# S7G2_footprint_with_caps.net
KiCad netlist of a schematic drawn in EAGLE
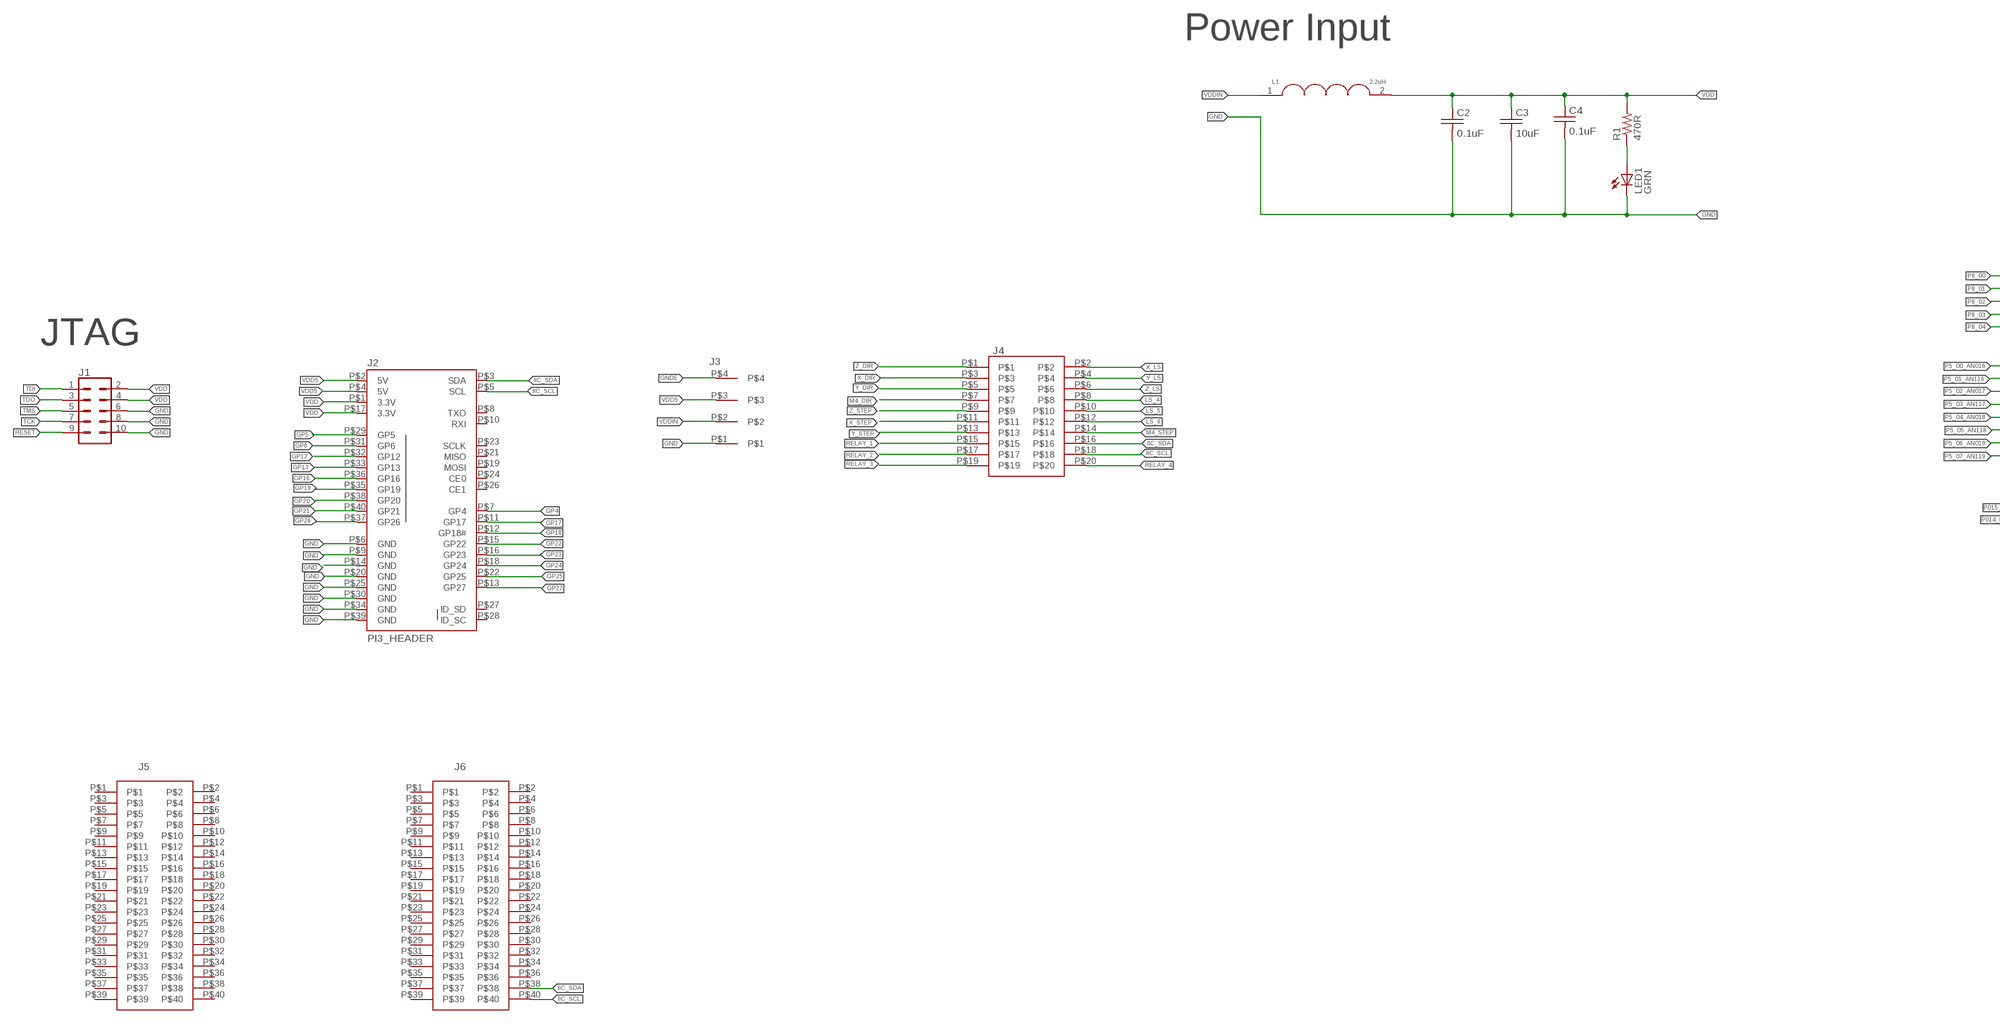
[diagram p0: schematic, sheet 1, part 1 of 3]
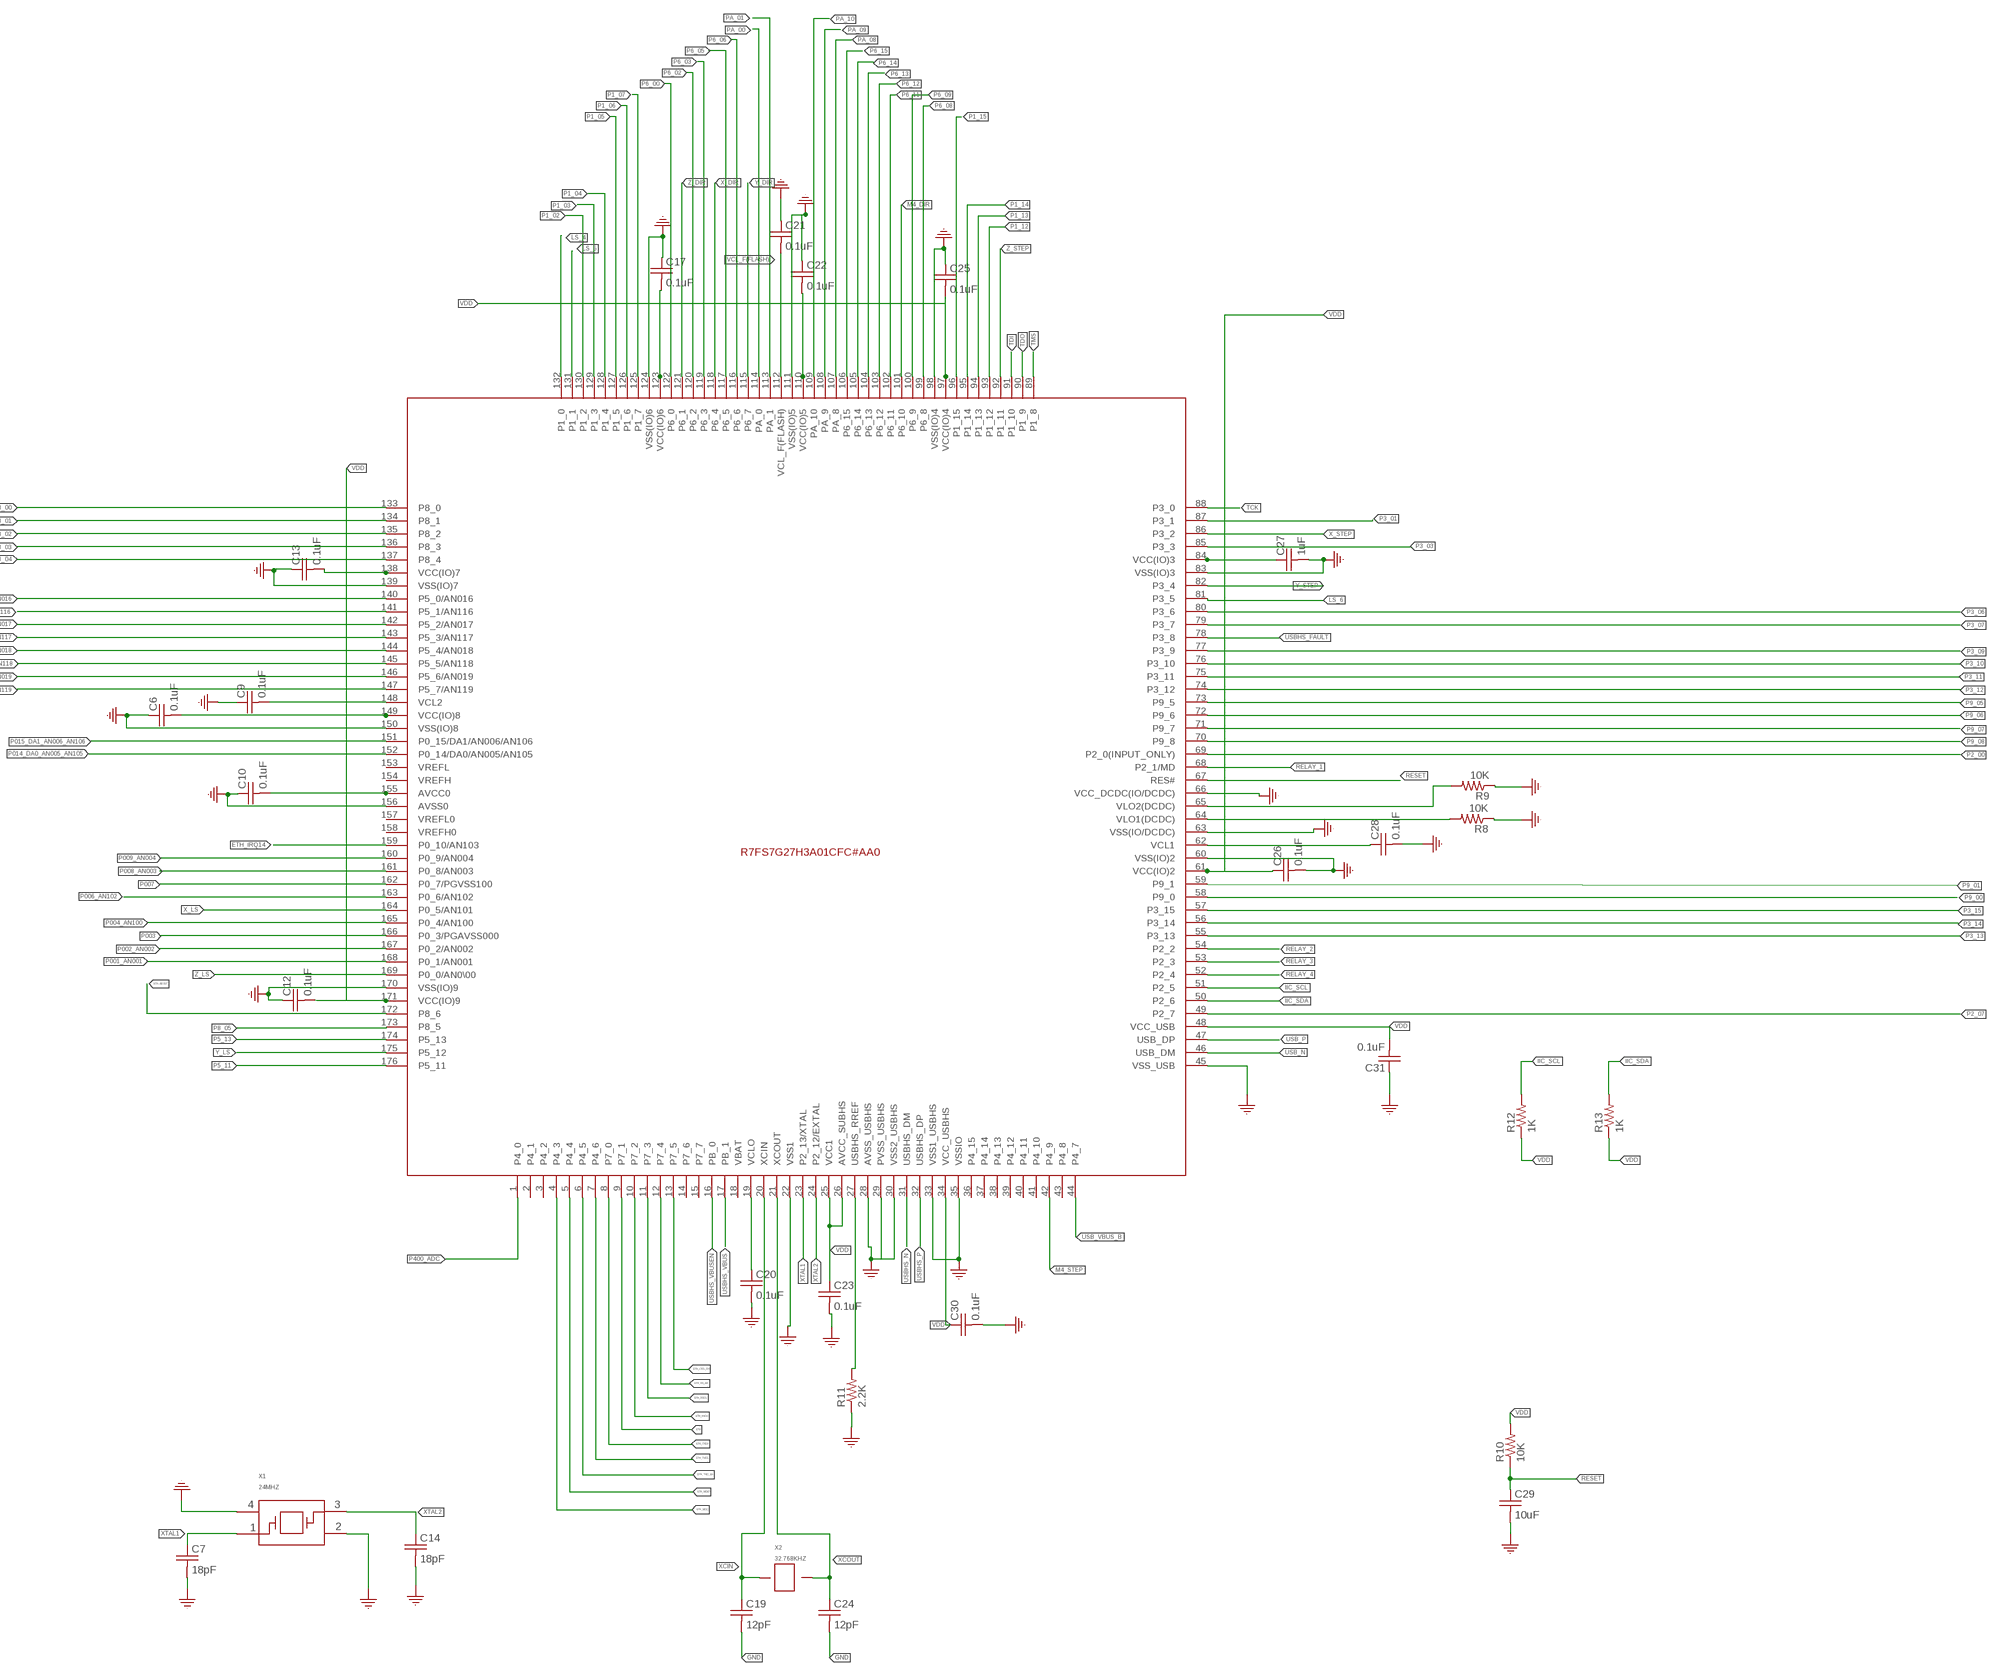
[diagram p1: schematic, sheet 1, part 2 of 3]
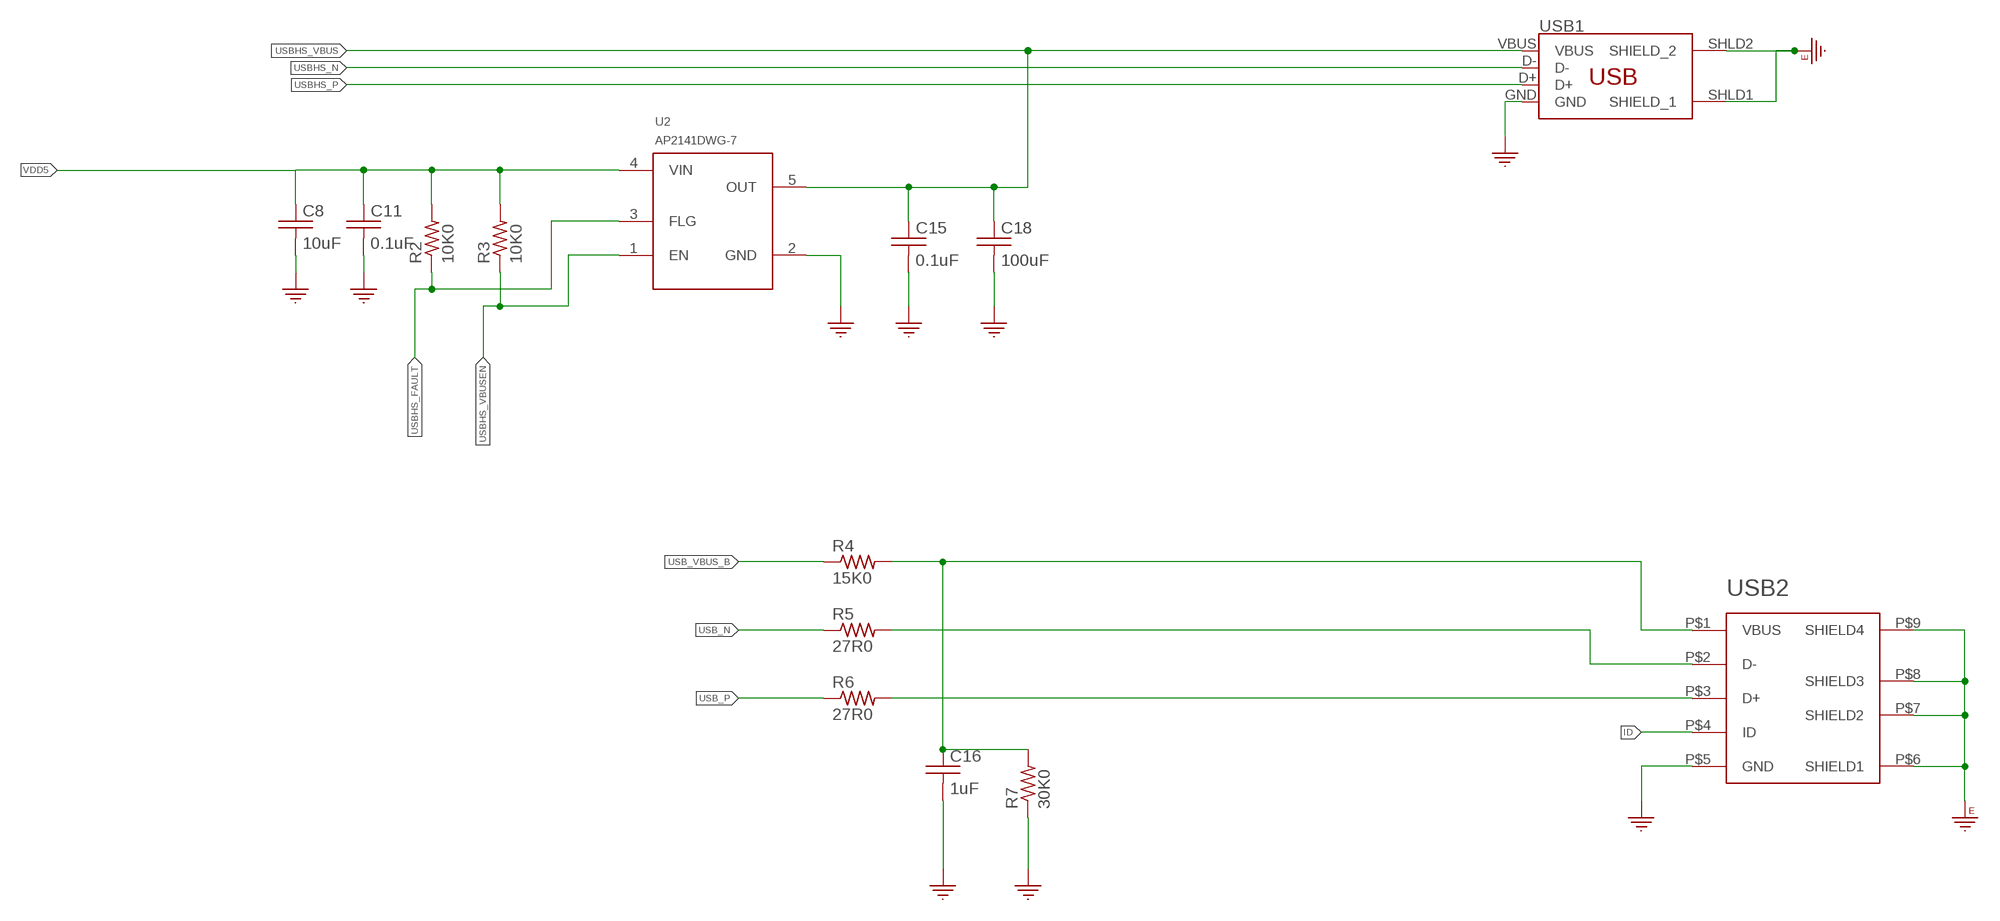
[diagram p2: schematic, sheet 1, part 3 of 3]

(export (version "E")
  (design (tool "Eeschema 10.0.6"))
  (components
    (comp (ref "C2")
      (value "0.1uF")
      (footprint "eagle-import:0402")
      (libsource (lib "eagle-import") (part "C_0402"))
    )
    (comp (ref "C3")
      (value "10uF")
      (footprint "eagle-import:0402")
      (libsource (lib "eagle-import") (part "C_0402"))
    )
    (comp (ref "C4")
      (value "0.1uF")
      (footprint "eagle-import:0402")
      (libsource (lib "eagle-import") (part "C_0402"))
    )
    (comp (ref "C6")
      (value "0.1uF")
      (footprint "eagle-import:0402")
      (libsource (lib "eagle-import") (part "C_0402"))
    )
    (comp (ref "C7")
      (value "18pF")
      (footprint "eagle-import:0402")
      (libsource (lib "eagle-import") (part "C_0402"))
    )
    (comp (ref "C8")
      (value "10uF")
      (footprint "eagle-import:0402")
      (libsource (lib "eagle-import") (part "C_0402"))
    )
    (comp (ref "C9")
      (value "0.1uF")
      (footprint "eagle-import:0402")
      (libsource (lib "eagle-import") (part "C_0402"))
    )
    (comp (ref "C10")
      (value "0.1uF")
      (footprint "eagle-import:0402")
      (libsource (lib "eagle-import") (part "C_0402"))
    )
    (comp (ref "C11")
      (value "0.1uF")
      (footprint "eagle-import:0402")
      (libsource (lib "eagle-import") (part "C_0402"))
    )
    (comp (ref "C12")
      (value "0.1uF")
      (footprint "eagle-import:0402")
      (libsource (lib "eagle-import") (part "C_0402"))
    )
    (comp (ref "C13")
      (value "0.1uF")
      (footprint "eagle-import:0402")
      (libsource (lib "eagle-import") (part "C_0402"))
    )
    (comp (ref "C14")
      (value "18pF")
      (footprint "eagle-import:0402")
      (libsource (lib "eagle-import") (part "C_0402"))
    )
    (comp (ref "C15")
      (value "0.1uF")
      (footprint "eagle-import:0402")
      (libsource (lib "eagle-import") (part "C_0402"))
    )
    (comp (ref "C16")
      (value "1uF")
      (footprint "eagle-import:0402")
      (libsource (lib "eagle-import") (part "C_0402"))
    )
    (comp (ref "C17")
      (value "0.1uF")
      (footprint "eagle-import:0402")
      (libsource (lib "eagle-import") (part "C_0402"))
    )
    (comp (ref "C18")
      (value "100uF")
      (footprint "eagle-import:C1210")
      (libsource (lib "eagle-import") (part "C_1210"))
    )
    (comp (ref "C19")
      (value "12pF")
      (footprint "eagle-import:0402")
      (libsource (lib "eagle-import") (part "C_0402"))
    )
    (comp (ref "C20")
      (value "0.1uF")
      (footprint "eagle-import:0402")
      (libsource (lib "eagle-import") (part "C_0402"))
    )
    (comp (ref "C21")
      (value "0.1uF")
      (footprint "eagle-import:0402")
      (libsource (lib "eagle-import") (part "C_0402"))
    )
    (comp (ref "C22")
      (value "0.1uF")
      (footprint "eagle-import:0402")
      (libsource (lib "eagle-import") (part "C_0402"))
    )
    (comp (ref "C23")
      (value "0.1uF")
      (footprint "eagle-import:0402")
      (libsource (lib "eagle-import") (part "C_0402"))
    )
    (comp (ref "C24")
      (value "12pF")
      (footprint "eagle-import:0402")
      (libsource (lib "eagle-import") (part "C_0402"))
    )
    (comp (ref "C25")
      (value "0.1uF")
      (footprint "eagle-import:0402")
      (libsource (lib "eagle-import") (part "C_0402"))
    )
    (comp (ref "C26")
      (value "0.1uF")
      (footprint "eagle-import:0402")
      (libsource (lib "eagle-import") (part "C_0402"))
    )
    (comp (ref "C27")
      (value "1uF")
      (footprint "eagle-import:0402")
      (libsource (lib "eagle-import") (part "C_0402"))
    )
    (comp (ref "C28")
      (value "0.1uF")
      (footprint "eagle-import:0402")
      (libsource (lib "eagle-import") (part "C_0402"))
    )
    (comp (ref "C29")
      (value "10uF")
      (footprint "eagle-import:0402")
      (libsource (lib "eagle-import") (part "C_0402"))
    )
    (comp (ref "C30")
      (value "0.1uF")
      (footprint "eagle-import:0402")
      (libsource (lib "eagle-import") (part "C_0402"))
    )
    (comp (ref "C31")
      (value "0.1uF")
      (footprint "eagle-import:0402")
      (libsource (lib "eagle-import") (part "C_0402"))
    )
    (comp (ref "J1")
      (value "CONN_05X2PTH")
      (footprint "eagle-import:2X5")
      (libsource (lib "eagle-import") (part "CONN_05X2PTH"))
    )
    (comp (ref "J2")
      (value "PI3_HEADER")
      (footprint "eagle-import:HEADER_2_X_20_.1_INCH")
      (libsource (lib "eagle-import") (part "PI3_HEADER"))
    )
    (comp (ref "J3")
      (value "3.81MM_1_X_4_RT_ANGLE_PLUG_HEADER")
      (footprint "eagle-import:1X4_3.81MM_PITCH")
      (libsource (lib "eagle-import") (part "3.81MM_1_X_4_RT_ANGLE_PLUG_HEADER"))
    )
    (comp (ref "J4")
      (value "2_X_10_HEADER_GENERIC")
      (footprint "eagle-import:2_X_10_.1_INCH")
      (libsource (lib "eagle-import") (part "2_X_10_HEADER_GENERIC"))
    )
    (comp (ref "J5")
      (value "HEADER_2_X_20_GENERIC")
      (footprint "eagle-import:HEADER_2_X_20_.1_INCH")
      (libsource (lib "eagle-import") (part "HEADER_2_X_20_GENERIC"))
    )
    (comp (ref "J6")
      (value "HEADER_2_X_20_GENERIC")
      (footprint "eagle-import:HEADER_2_X_20_.1_INCH")
      (libsource (lib "eagle-import") (part "HEADER_2_X_20_GENERIC"))
    )
    (comp (ref "L1")
      (value "2.2uH")
      (footprint "eagle-import:1008_(2520_METRIC)")
      (libsource (lib "eagle-import") (part "INDUCTOR_1008_2.2_MH_1.3A"))
    )
    (comp (ref "LED1")
      (value "LED_0805_GREEN")
      (footprint "eagle-import:LED_0805_GREEN")
      (libsource (lib "eagle-import") (part "LED_0805_GREEN"))
    )
    (comp (ref "R1")
      (value "470R")
      (footprint "eagle-import:0402")
      (libsource (lib "eagle-import") (part "R_0402"))
    )
    (comp (ref "R2")
      (value "10K0")
      (footprint "eagle-import:0402")
      (libsource (lib "eagle-import") (part "R_0402"))
    )
    (comp (ref "R3")
      (value "10K0")
      (footprint "eagle-import:0402")
      (libsource (lib "eagle-import") (part "R_0402"))
    )
    (comp (ref "R4")
      (value "15K0")
      (footprint "eagle-import:0402")
      (libsource (lib "eagle-import") (part "R_0402"))
    )
    (comp (ref "R5")
      (value "27R0")
      (footprint "eagle-import:0402")
      (libsource (lib "eagle-import") (part "R_0402"))
    )
    (comp (ref "R6")
      (value "27R0")
      (footprint "eagle-import:0402")
      (libsource (lib "eagle-import") (part "R_0402"))
    )
    (comp (ref "R7")
      (value "30K0")
      (footprint "eagle-import:0402")
      (libsource (lib "eagle-import") (part "R_0402"))
    )
    (comp (ref "R8")
      (value "10K")
      (footprint "eagle-import:0402")
      (libsource (lib "eagle-import") (part "R_0402"))
    )
    (comp (ref "R9")
      (value "10K")
      (footprint "eagle-import:0402")
      (libsource (lib "eagle-import") (part "R_0402"))
    )
    (comp (ref "R10")
      (value "10K")
      (footprint "eagle-import:0402")
      (libsource (lib "eagle-import") (part "R_0402"))
    )
    (comp (ref "R11")
      (value "2.2K")
      (footprint "eagle-import:0402")
      (libsource (lib "eagle-import") (part "R_0402"))
    )
    (comp (ref "R12")
      (value "1K")
      (footprint "eagle-import:0402")
      (libsource (lib "eagle-import") (part "R_0402"))
    )
    (comp (ref "R13")
      (value "1K")
      (footprint "eagle-import:0402")
      (libsource (lib "eagle-import") (part "R_0402"))
    )
    (comp (ref "U2")
      (value "AP2141DWG-5")
      (footprint "eagle-import:SOT-23-5")
      (libsource (lib "eagle-import") (part "AP2141DWG-5"))
    )
    (comp (ref "U5")
      (value "S7G2_X_176")
      (footprint "eagle-import:LQFP176_24X24")
      (libsource (lib "eagle-import") (part "S7G2_X_176"))
    )
    (comp (ref "USB1")
      (value "USB_A")
      (footprint "eagle-import:USB_A_SMT")
      (libsource (lib "eagle-import") (part "USB_A"))
    )
    (comp (ref "USB2")
      (value "USB_MICRO-B")
      (footprint "eagle-import:USB_MICRO-B")
      (libsource (lib "eagle-import") (part "USB_MICRO-B"))
    )
    (comp (ref "X1")
      (value "24MHZ")
      (footprint "eagle-import:SMD_3225")
      (libsource (lib "eagle-import") (part "XTAL_24_MHZ"))
    )
    (comp (ref "X2")
      (value "32.768KHZ")
      (footprint "eagle-import:SMD_X_2_PADS")
      (libsource (lib "eagle-import") (part "XTAL_32.768KHZ"))
    )
  )
  (nets
    (net (code "1") (name "ETH") (class "Default")
      (node (ref "U5") (pin "9") (pinfunction "P7_1_9") (pintype "bidirectional"))
    )
    (net (code "2") (name "ETH_CRS_DV") (class "Default")
      (node (ref "U5") (pin "13") (pinfunction "P7_5_13") (pintype "bidirectional"))
    )
    (net (code "3") (name "ETH_IRQ14") (class "Default")
      (node (ref "U5") (pin "159") (pinfunction "P0_10/AN103_159") (pintype "bidirectional"))
    )
    (net (code "4") (name "ETH_MDC") (class "Default")
      (node (ref "U5") (pin "4") (pinfunction "P4_3_4") (pintype "bidirectional"))
    )
    (net (code "5") (name "ETH_MDIO") (class "Default")
      (node (ref "U5") (pin "5") (pinfunction "P4_4_5") (pintype "bidirectional"))
    )
    (net (code "6") (name "ETH_RESET") (class "Default")
      (node (ref "U5") (pin "172") (pinfunction "P8_6_172") (pintype "bidirectional"))
    )
    (net (code "7") (name "ETH_RXD0") (class "Default")
      (node (ref "U5") (pin "10") (pinfunction "P7_2_10") (pintype "bidirectional"))
    )
    (net (code "8") (name "ETH_RXD1") (class "Default")
      (node (ref "U5") (pin "11") (pinfunction "P7_3_11") (pintype "bidirectional"))
    )
    (net (code "9") (name "ETH_RX_ER") (class "Default")
      (node (ref "U5") (pin "12") (pinfunction "P7_4_12") (pintype "bidirectional"))
    )
    (net (code "10") (name "ETH_TXD0") (class "Default")
      (node (ref "U5") (pin "8") (pinfunction "P7_0_8") (pintype "bidirectional"))
    )
    (net (code "11") (name "ETH_TXD1") (class "Default")
      (node (ref "U5") (pin "7") (pinfunction "P4_6_7") (pintype "bidirectional"))
    )
    (net (code "12") (name "ETH_TXD_EN") (class "Default")
      (node (ref "U5") (pin "6") (pinfunction "P4_5_6") (pintype "bidirectional"))
    )
    (net (code "13") (name "GND") (class "Default")
      (node (ref "C10") (pin "P$1") (pinfunction "1_P$1") (pintype "passive"))
      (node (ref "C11") (pin "P$2") (pinfunction "2_P$2") (pintype "passive"))
      (node (ref "C12") (pin "P$1") (pinfunction "1_P$1") (pintype "passive"))
      (node (ref "C13") (pin "P$1") (pinfunction "1_P$1") (pintype "passive"))
      (node (ref "C14") (pin "P$2") (pinfunction "2_P$2") (pintype "passive"))
      (node (ref "C15") (pin "P$2") (pinfunction "2_P$2") (pintype "passive"))
      (node (ref "C16") (pin "P$2") (pinfunction "2_P$2") (pintype "passive"))
      (node (ref "C17") (pin "P$1") (pinfunction "1_P$1") (pintype "passive"))
      (node (ref "C18") (pin "2") (pinfunction "2_2") (pintype "passive"))
      (node (ref "C19") (pin "P$2") (pinfunction "2_P$2") (pintype "passive"))
      (node (ref "C2") (pin "P$2") (pinfunction "2_P$2") (pintype "passive"))
      (node (ref "C20") (pin "P$2") (pinfunction "2_P$2") (pintype "passive"))
      (node (ref "C21") (pin "P$1") (pinfunction "1_P$1") (pintype "passive"))
      (node (ref "C22") (pin "P$1") (pinfunction "1_P$1") (pintype "passive"))
      (node (ref "C23") (pin "P$2") (pinfunction "2_P$2") (pintype "passive"))
      (node (ref "C24") (pin "P$2") (pinfunction "2_P$2") (pintype "passive"))
      (node (ref "C25") (pin "P$1") (pinfunction "1_P$1") (pintype "passive"))
      (node (ref "C26") (pin "P$2") (pinfunction "2_P$2") (pintype "passive"))
      (node (ref "C27") (pin "P$2") (pinfunction "2_P$2") (pintype "passive"))
      (node (ref "C28") (pin "P$2") (pinfunction "2_P$2") (pintype "passive"))
      (node (ref "C29") (pin "P$2") (pinfunction "2_P$2") (pintype "passive"))
      (node (ref "C3") (pin "P$2") (pinfunction "2_P$2") (pintype "passive"))
      (node (ref "C30") (pin "P$2") (pinfunction "2_P$2") (pintype "passive"))
      (node (ref "C31") (pin "P$1") (pinfunction "1_P$1") (pintype "passive"))
      (node (ref "C4") (pin "P$2") (pinfunction "2_P$2") (pintype "passive"))
      (node (ref "C6") (pin "P$1") (pinfunction "1_P$1") (pintype "passive"))
      (node (ref "C7") (pin "P$2") (pinfunction "2_P$2") (pintype "passive"))
      (node (ref "C8") (pin "P$2") (pinfunction "2_P$2") (pintype "passive"))
      (node (ref "C9") (pin "P$1") (pinfunction "1_P$1") (pintype "passive"))
      (node (ref "J1") (pin "10") (pinfunction "10_10") (pintype "passive"))
      (node (ref "J1") (pin "6") (pinfunction "6_6") (pintype "passive"))
      (node (ref "J1") (pin "8") (pinfunction "8_8") (pintype "passive"))
      (node (ref "J2") (pin "P$14") (pinfunction "GND_P$14") (pintype "power_in"))
      (node (ref "J2") (pin "P$20") (pinfunction "GND_P$20") (pintype "power_in"))
      (node (ref "J2") (pin "P$25") (pinfunction "GND_P$25") (pintype "power_in"))
      (node (ref "J2") (pin "P$30") (pinfunction "GND_P$30") (pintype "power_in"))
      (node (ref "J2") (pin "P$34") (pinfunction "GND_P$34") (pintype "power_in"))
      (node (ref "J2") (pin "P$39") (pinfunction "GND_P$39") (pintype "power_in"))
      (node (ref "J2") (pin "P$6") (pinfunction "GND_P$6") (pintype "power_in"))
      (node (ref "J2") (pin "P$9") (pinfunction "GND_P$9") (pintype "power_in"))
      (node (ref "J3") (pin "P$1") (pinfunction "P$1_P$1") (pintype "bidirectional"))
      (node (ref "LED1") (pin "C") (pinfunction "C_C") (pintype "passive"))
      (node (ref "R11") (pin "P$1") (pinfunction "1_P$1") (pintype "passive"))
      (node (ref "R7") (pin "P$1") (pinfunction "1_P$1") (pintype "passive"))
      (node (ref "R8") (pin "P$1") (pinfunction "1_P$1") (pintype "passive"))
      (node (ref "R9") (pin "P$1") (pinfunction "1_P$1") (pintype "passive"))
      (node (ref "U2") (pin "2") (pinfunction "GND_2") (pintype "input"))
      (node (ref "U5") (pin "111") (pinfunction "VSS(IO)5_111") (pintype "bidirectional"))
      (node (ref "U5") (pin "124") (pinfunction "VSS(IO)6_124") (pintype "bidirectional"))
      (node (ref "U5") (pin "139") (pinfunction "VSS(IO)7_139") (pintype "bidirectional"))
      (node (ref "U5") (pin "150") (pinfunction "VSS(IO)8_150") (pintype "bidirectional"))
      (node (ref "U5") (pin "156") (pinfunction "AVSS0_156") (pintype "bidirectional"))
      (node (ref "U5") (pin "170") (pinfunction "VSS(IO)9_170") (pintype "bidirectional"))
      (node (ref "U5") (pin "22") (pinfunction "VSS1_22") (pintype "bidirectional"))
      (node (ref "U5") (pin "28") (pinfunction "AVSS_USBHS_28") (pintype "bidirectional"))
      (node (ref "U5") (pin "29") (pinfunction "PVSS_USBHS_29") (pintype "bidirectional"))
      (node (ref "U5") (pin "30") (pinfunction "VSS2_USBHS_30") (pintype "bidirectional"))
      (node (ref "U5") (pin "33") (pinfunction "VSS1_USBHS_33") (pintype "bidirectional"))
      (node (ref "U5") (pin "35") (pinfunction "VSSIO_35") (pintype "bidirectional"))
      (node (ref "U5") (pin "45") (pinfunction "VSS_USB_45") (pintype "bidirectional"))
      (node (ref "U5") (pin "60") (pinfunction "VSS(IO)2_60") (pintype "bidirectional"))
      (node (ref "U5") (pin "63") (pinfunction "VSS(IO/DCDC)_63") (pintype "bidirectional"))
      (node (ref "U5") (pin "66") (pinfunction "VCC_DCDC(IO/DCDC)_66") (pintype "bidirectional"))
      (node (ref "U5") (pin "83") (pinfunction "VSS(IO)3_83") (pintype "bidirectional"))
      (node (ref "U5") (pin "98") (pinfunction "VSS(IO)4_98") (pintype "bidirectional"))
      (node (ref "USB1") (pin "GND") (pinfunction "GND_GND") (pintype "power_in"))
      (node (ref "USB2") (pin "P$5") (pinfunction "GND_P$5") (pintype "bidirectional"))
      (node (ref "X1") (pin "2") (pinfunction "2_2") (pintype "bidirectional"))
      (node (ref "X1") (pin "4") (pinfunction "4_4") (pintype "bidirectional"))
    )
    (net (code "14") (name "GNDE") (class "Default")
      (node (ref "J3") (pin "P$4") (pinfunction "P$4_P$4") (pintype "bidirectional"))
      (node (ref "USB1") (pin "SHLD1") (pinfunction "SHIELD_1_SHLD1") (pintype "bidirectional"))
      (node (ref "USB1") (pin "SHLD2") (pinfunction "SHIELD_2_SHLD2") (pintype "bidirectional"))
      (node (ref "USB2") (pin "P$6") (pinfunction "SHIELD1_P$6") (pintype "bidirectional"))
      (node (ref "USB2") (pin "P$7") (pinfunction "SHIELD2_P$7") (pintype "bidirectional"))
      (node (ref "USB2") (pin "P$8") (pinfunction "SHIELD3_P$8") (pintype "bidirectional"))
      (node (ref "USB2") (pin "P$9") (pinfunction "SHIELD4_P$9") (pintype "bidirectional"))
    )
    (net (code "15") (name "GP4") (class "Default")
      (node (ref "J2") (pin "P$7") (pinfunction "GP4_P$7") (pintype "bidirectional"))
    )
    (net (code "16") (name "GP5") (class "Default")
      (node (ref "J2") (pin "P$29") (pinfunction "GP5_P$29") (pintype "bidirectional"))
    )
    (net (code "17") (name "GP6") (class "Default")
      (node (ref "J2") (pin "P$31") (pinfunction "GP6_P$31") (pintype "bidirectional"))
    )
    (net (code "18") (name "GP12") (class "Default")
      (node (ref "J2") (pin "P$32") (pinfunction "GP12_P$32") (pintype "bidirectional"))
    )
    (net (code "19") (name "GP13") (class "Default")
      (node (ref "J2") (pin "P$33") (pinfunction "GP13_P$33") (pintype "bidirectional"))
    )
    (net (code "20") (name "GP16") (class "Default")
      (node (ref "J2") (pin "P$36") (pinfunction "GP16_P$36") (pintype "bidirectional"))
    )
    (net (code "21") (name "GP17") (class "Default")
      (node (ref "J2") (pin "P$11") (pinfunction "GP17_P$11") (pintype "bidirectional"))
    )
    (net (code "22") (name "GP18") (class "Default")
      (node (ref "J2") (pin "P$12") (pinfunction "GP18#_P$12") (pintype "bidirectional"))
    )
    (net (code "23") (name "GP19") (class "Default")
      (node (ref "J2") (pin "P$35") (pinfunction "GP19_P$35") (pintype "bidirectional"))
    )
    (net (code "24") (name "GP20") (class "Default")
      (node (ref "J2") (pin "P$38") (pinfunction "GP20_P$38") (pintype "bidirectional"))
    )
    (net (code "25") (name "GP21") (class "Default")
      (node (ref "J2") (pin "P$40") (pinfunction "GP21_P$40") (pintype "bidirectional"))
    )
    (net (code "26") (name "GP22") (class "Default")
      (node (ref "J2") (pin "P$15") (pinfunction "GP22_P$15") (pintype "bidirectional"))
    )
    (net (code "27") (name "GP23") (class "Default")
      (node (ref "J2") (pin "P$16") (pinfunction "GP23_P$16") (pintype "bidirectional"))
    )
    (net (code "28") (name "GP24") (class "Default")
      (node (ref "J2") (pin "P$18") (pinfunction "GP24_P$18") (pintype "bidirectional"))
    )
    (net (code "29") (name "GP25") (class "Default")
      (node (ref "J2") (pin "P$22") (pinfunction "GP25_P$22") (pintype "bidirectional"))
    )
    (net (code "30") (name "GP26") (class "Default")
      (node (ref "J2") (pin "P$37") (pinfunction "GP26_P$37") (pintype "bidirectional"))
    )
    (net (code "31") (name "GP27") (class "Default")
      (node (ref "J2") (pin "P$13") (pinfunction "GP27_P$13") (pintype "bidirectional"))
    )
    (net (code "32") (name "ID") (class "Default")
      (node (ref "USB2") (pin "P$4") (pinfunction "ID_P$4") (pintype "bidirectional"))
    )
    (net (code "33") (name "IIC_SCL") (class "Default")
      (node (ref "J2") (pin "P$5") (pinfunction "SCL_P$5") (pintype "bidirectional"))
      (node (ref "J4") (pin "P$18") (pinfunction "P$18_P$18") (pintype "bidirectional"))
      (node (ref "J6") (pin "P$40") (pinfunction "P$40_P$40") (pintype "bidirectional"))
      (node (ref "R12") (pin "P$2") (pinfunction "2_P$2") (pintype "passive"))
      (node (ref "U5") (pin "51") (pinfunction "P2_5_51") (pintype "bidirectional"))
    )
    (net (code "34") (name "IIC_SDA") (class "Default")
      (node (ref "J2") (pin "P$3") (pinfunction "SDA_P$3") (pintype "bidirectional"))
      (node (ref "J4") (pin "P$16") (pinfunction "P$16_P$16") (pintype "bidirectional"))
      (node (ref "J6") (pin "P$38") (pinfunction "P$38_P$38") (pintype "bidirectional"))
      (node (ref "R13") (pin "P$2") (pinfunction "2_P$2") (pintype "passive"))
      (node (ref "U5") (pin "50") (pinfunction "P2_6_50") (pintype "bidirectional"))
    )
    (net (code "35") (name "LS_4") (class "Default")
      (node (ref "J4") (pin "P$8") (pinfunction "P$8_P$8") (pintype "bidirectional"))
      (node (ref "U5") (pin "132") (pinfunction "P1_0_132") (pintype "bidirectional"))
    )
    (net (code "36") (name "LS_5") (class "Default")
      (node (ref "J4") (pin "P$10") (pinfunction "P$10_P$10") (pintype "bidirectional"))
      (node (ref "U5") (pin "131") (pinfunction "P1_1_131") (pintype "bidirectional"))
    )
    (net (code "37") (name "LS_6") (class "Default")
      (node (ref "J4") (pin "P$12") (pinfunction "P$12_P$12") (pintype "bidirectional"))
      (node (ref "U5") (pin "81") (pinfunction "P3_5_81") (pintype "bidirectional"))
    )
    (net (code "38") (name "M4_DIR") (class "Default")
      (node (ref "J4") (pin "P$7") (pinfunction "P$7_P$7") (pintype "bidirectional"))
      (node (ref "U5") (pin "101") (pinfunction "P6_10_101") (pintype "bidirectional"))
    )
    (net (code "39") (name "M4_STEP") (class "Default")
      (node (ref "J4") (pin "P$14") (pinfunction "P$14_P$14") (pintype "bidirectional"))
      (node (ref "U5") (pin "42") (pinfunction "P4_9_42") (pintype "bidirectional"))
    )
    (net (code "40") (name "Net-(C9-2)") (class "Default")
      (node (ref "C9") (pin "P$2") (pinfunction "2_P$2") (pintype "passive"))
      (node (ref "U5") (pin "148") (pinfunction "VCL2_148") (pintype "bidirectional"))
    )
    (net (code "41") (name "Net-(C16-1)") (class "Default")
      (node (ref "C16") (pin "P$1") (pinfunction "1_P$1") (pintype "passive"))
      (node (ref "R4") (pin "P$2") (pinfunction "2_P$2") (pintype "passive"))
      (node (ref "R7") (pin "P$2") (pinfunction "2_P$2") (pintype "passive"))
      (node (ref "USB2") (pin "P$1") (pinfunction "VBUS_P$1") (pintype "bidirectional"))
    )
    (net (code "42") (name "Net-(C20-1)") (class "Default")
      (node (ref "C20") (pin "P$1") (pinfunction "1_P$1") (pintype "passive"))
      (node (ref "U5") (pin "19") (pinfunction "VCLO_19") (pintype "bidirectional"))
    )
    (net (code "43") (name "Net-(C28-1)") (class "Default")
      (node (ref "C28") (pin "P$1") (pinfunction "1_P$1") (pintype "passive"))
      (node (ref "U5") (pin "62") (pinfunction "VCL1_62") (pintype "bidirectional"))
    )
    (net (code "44") (name "Net-(R1-1)") (class "Default")
      (node (ref "LED1") (pin "A") (pinfunction "A_A") (pintype "passive"))
      (node (ref "R1") (pin "P$1") (pinfunction "1_P$1") (pintype "passive"))
    )
    (net (code "45") (name "Net-(R5-2)") (class "Default")
      (node (ref "R5") (pin "P$2") (pinfunction "2_P$2") (pintype "passive"))
      (node (ref "USB2") (pin "P$2") (pinfunction "D-_P$2") (pintype "bidirectional"))
    )
    (net (code "46") (name "Net-(R6-2)") (class "Default")
      (node (ref "R6") (pin "P$2") (pinfunction "2_P$2") (pintype "passive"))
      (node (ref "USB2") (pin "P$3") (pinfunction "D+_P$3") (pintype "bidirectional"))
    )
    (net (code "47") (name "Net-(R8-2)") (class "Default")
      (node (ref "R8") (pin "P$2") (pinfunction "2_P$2") (pintype "passive"))
      (node (ref "U5") (pin "64") (pinfunction "VLO1(DCDC)_64") (pintype "bidirectional"))
    )
    (net (code "48") (name "Net-(R9-2)") (class "Default")
      (node (ref "R9") (pin "P$2") (pinfunction "2_P$2") (pintype "passive"))
      (node (ref "U5") (pin "65") (pinfunction "VLO2(DCDC)_65") (pintype "bidirectional"))
    )
    (net (code "49") (name "Net-(R11-2)") (class "Default")
      (node (ref "R11") (pin "P$2") (pinfunction "2_P$2") (pintype "passive"))
      (node (ref "U5") (pin "27") (pinfunction "USBHS_RREF_27") (pintype "bidirectional"))
    )
    (net (code "50") (name "P1_02") (class "Default")
      (node (ref "U5") (pin "130") (pinfunction "P1_2_130") (pintype "bidirectional"))
    )
    (net (code "51") (name "P1_03") (class "Default")
      (node (ref "U5") (pin "129") (pinfunction "P1_3_129") (pintype "bidirectional"))
    )
    (net (code "52") (name "P1_04") (class "Default")
      (node (ref "U5") (pin "128") (pinfunction "P1_4_128") (pintype "bidirectional"))
    )
    (net (code "53") (name "P1_05") (class "Default")
      (node (ref "U5") (pin "127") (pinfunction "P1_5_127") (pintype "bidirectional"))
    )
    (net (code "54") (name "P1_06") (class "Default")
      (node (ref "U5") (pin "126") (pinfunction "P1_6_126") (pintype "bidirectional"))
    )
    (net (code "55") (name "P1_07") (class "Default")
      (node (ref "U5") (pin "125") (pinfunction "P1_7_125") (pintype "bidirectional"))
    )
    (net (code "56") (name "P1_12") (class "Default")
      (node (ref "U5") (pin "93") (pinfunction "P1_12_93") (pintype "bidirectional"))
    )
    (net (code "57") (name "P1_13") (class "Default")
      (node (ref "U5") (pin "94") (pinfunction "P1_13_94") (pintype "bidirectional"))
    )
    (net (code "58") (name "P1_14") (class "Default")
      (node (ref "U5") (pin "95") (pinfunction "P1_14_95") (pintype "bidirectional"))
    )
    (net (code "59") (name "P1_15") (class "Default")
      (node (ref "U5") (pin "96") (pinfunction "P1_15_96") (pintype "bidirectional"))
    )
    (net (code "60") (name "P001_AN001") (class "Default")
      (node (ref "U5") (pin "168") (pinfunction "P0_1/AN001_168") (pintype "bidirectional"))
    )
    (net (code "61") (name "P2_00") (class "Default")
      (node (ref "U5") (pin "69") (pinfunction "P2_0(INPUT_ONLY)_69") (pintype "bidirectional"))
    )
    (net (code "62") (name "P2_07") (class "Default")
      (node (ref "U5") (pin "49") (pinfunction "P2_7_49") (pintype "bidirectional"))
    )
    (net (code "63") (name "P002_AN002") (class "Default")
      (node (ref "U5") (pin "167") (pinfunction "P0_2/AN002_167") (pintype "bidirectional"))
    )
    (net (code "64") (name "P003") (class "Default")
      (node (ref "U5") (pin "166") (pinfunction "P0_3/PGAVSS000_166") (pintype "bidirectional"))
    )
    (net (code "65") (name "P3_01") (class "Default")
      (node (ref "U5") (pin "87") (pinfunction "P3_1_87") (pintype "bidirectional"))
    )
    (net (code "66") (name "P3_03") (class "Default")
      (node (ref "U5") (pin "85") (pinfunction "P3_3_85") (pintype "bidirectional"))
    )
    (net (code "67") (name "P3_06") (class "Default")
      (node (ref "U5") (pin "80") (pinfunction "P3_6_80") (pintype "bidirectional"))
    )
    (net (code "68") (name "P3_07") (class "Default")
      (node (ref "U5") (pin "79") (pinfunction "P3_7_79") (pintype "bidirectional"))
    )
    (net (code "69") (name "P3_09") (class "Default")
      (node (ref "U5") (pin "77") (pinfunction "P3_9_77") (pintype "bidirectional"))
    )
    (net (code "70") (name "P3_10") (class "Default")
      (node (ref "U5") (pin "76") (pinfunction "P3_10_76") (pintype "bidirectional"))
    )
    (net (code "71") (name "P3_11") (class "Default")
      (node (ref "U5") (pin "75") (pinfunction "P3_11_75") (pintype "bidirectional"))
    )
    (net (code "72") (name "P3_12") (class "Default")
      (node (ref "U5") (pin "74") (pinfunction "P3_12_74") (pintype "bidirectional"))
    )
    (net (code "73") (name "P3_13") (class "Default")
      (node (ref "U5") (pin "55") (pinfunction "P3_13_55") (pintype "bidirectional"))
    )
    (net (code "74") (name "P3_14") (class "Default")
      (node (ref "U5") (pin "56") (pinfunction "P3_14_56") (pintype "bidirectional"))
    )
    (net (code "75") (name "P3_15") (class "Default")
      (node (ref "U5") (pin "57") (pinfunction "P3_15_57") (pintype "bidirectional"))
    )
    (net (code "76") (name "P004_AN100") (class "Default")
      (node (ref "U5") (pin "165") (pinfunction "P0_4/AN100_165") (pintype "bidirectional"))
    )
    (net (code "77") (name "P5_00_AN016") (class "Default")
      (node (ref "U5") (pin "140") (pinfunction "P5_0/AN016_140") (pintype "bidirectional"))
    )
    (net (code "78") (name "P5_01_AN116") (class "Default")
      (node (ref "U5") (pin "141") (pinfunction "P5_1/AN116_141") (pintype "bidirectional"))
    )
    (net (code "79") (name "P5_02_AN017") (class "Default")
      (node (ref "U5") (pin "142") (pinfunction "P5_2/AN017_142") (pintype "bidirectional"))
    )
    (net (code "80") (name "P5_03_AN117") (class "Default")
      (node (ref "U5") (pin "143") (pinfunction "P5_3/AN117_143") (pintype "bidirectional"))
    )
    (net (code "81") (name "P5_04_AN018") (class "Default")
      (node (ref "U5") (pin "144") (pinfunction "P5_4/AN018_144") (pintype "bidirectional"))
    )
    (net (code "82") (name "P5_05_AN118") (class "Default")
      (node (ref "U5") (pin "145") (pinfunction "P5_5/AN118_145") (pintype "bidirectional"))
    )
    (net (code "83") (name "P5_06_AN019") (class "Default")
      (node (ref "U5") (pin "146") (pinfunction "P5_6/AN019_146") (pintype "bidirectional"))
    )
    (net (code "84") (name "P5_07_AN119") (class "Default")
      (node (ref "U5") (pin "147") (pinfunction "P5_7/AN119_147") (pintype "bidirectional"))
    )
    (net (code "85") (name "P5_11") (class "Default")
      (node (ref "U5") (pin "176") (pinfunction "P5_11_176") (pintype "bidirectional"))
    )
    (net (code "86") (name "P5_13") (class "Default")
      (node (ref "U5") (pin "174") (pinfunction "P5_13_174") (pintype "bidirectional"))
    )
    (net (code "87") (name "P6_00") (class "Default")
      (node (ref "U5") (pin "122") (pinfunction "P6_0_122") (pintype "bidirectional"))
    )
    (net (code "88") (name "P6_02") (class "Default")
      (node (ref "U5") (pin "120") (pinfunction "P6_2_120") (pintype "bidirectional"))
    )
    (net (code "89") (name "P6_03") (class "Default")
      (node (ref "U5") (pin "119") (pinfunction "P6_3_119") (pintype "bidirectional"))
    )
    (net (code "90") (name "P6_05") (class "Default")
      (node (ref "U5") (pin "117") (pinfunction "P6_5_117") (pintype "bidirectional"))
    )
    (net (code "91") (name "P6_06") (class "Default")
      (node (ref "U5") (pin "116") (pinfunction "P6_6_116") (pintype "bidirectional"))
    )
    (net (code "92") (name "P6_08") (class "Default")
      (node (ref "U5") (pin "99") (pinfunction "P6_8_99") (pintype "bidirectional"))
    )
    (net (code "93") (name "P6_09") (class "Default")
      (node (ref "U5") (pin "100") (pinfunction "P6_9_100") (pintype "bidirectional"))
    )
    (net (code "94") (name "P6_11") (class "Default")
      (node (ref "U5") (pin "102") (pinfunction "P6_11_102") (pintype "bidirectional"))
    )
    (net (code "95") (name "P6_12") (class "Default")
      (node (ref "U5") (pin "103") (pinfunction "P6_12_103") (pintype "bidirectional"))
    )
    (net (code "96") (name "P6_13") (class "Default")
      (node (ref "U5") (pin "104") (pinfunction "P6_13_104") (pintype "bidirectional"))
    )
    (net (code "97") (name "P6_14") (class "Default")
      (node (ref "U5") (pin "105") (pinfunction "P6_14_105") (pintype "bidirectional"))
    )
    (net (code "98") (name "P6_15") (class "Default")
      (node (ref "U5") (pin "106") (pinfunction "P6_15_106") (pintype "bidirectional"))
    )
    (net (code "99") (name "P006_AN102") (class "Default")
      (node (ref "U5") (pin "163") (pinfunction "P0_6/AN102_163") (pintype "bidirectional"))
    )
    (net (code "100") (name "P007") (class "Default")
      (node (ref "U5") (pin "162") (pinfunction "P0_7/PGVSS100_162") (pintype "bidirectional"))
    )
    (net (code "101") (name "P8_00") (class "Default")
      (node (ref "U5") (pin "133") (pinfunction "P8_0_133") (pintype "bidirectional"))
    )
    (net (code "102") (name "P8_01") (class "Default")
      (node (ref "U5") (pin "134") (pinfunction "P8_1_134") (pintype "bidirectional"))
    )
    (net (code "103") (name "P8_02") (class "Default")
      (node (ref "U5") (pin "135") (pinfunction "P8_2_135") (pintype "bidirectional"))
    )
    (net (code "104") (name "P8_03") (class "Default")
      (node (ref "U5") (pin "136") (pinfunction "P8_3_136") (pintype "bidirectional"))
    )
    (net (code "105") (name "P8_04") (class "Default")
      (node (ref "U5") (pin "137") (pinfunction "P8_4_137") (pintype "bidirectional"))
    )
    (net (code "106") (name "P8_05") (class "Default")
      (node (ref "U5") (pin "173") (pinfunction "P8_5_173") (pintype "bidirectional"))
    )
    (net (code "107") (name "P008_AN003") (class "Default")
      (node (ref "U5") (pin "161") (pinfunction "P0_8/AN003_161") (pintype "bidirectional"))
    )
    (net (code "108") (name "P9_00") (class "Default")
      (node (ref "U5") (pin "58") (pinfunction "P9_0_58") (pintype "bidirectional"))
    )
    (net (code "109") (name "P9_01") (class "Default")
      (node (ref "U5") (pin "59") (pinfunction "P9_1_59") (pintype "bidirectional"))
    )
    (net (code "110") (name "P9_05") (class "Default")
      (node (ref "U5") (pin "73") (pinfunction "P9_5_73") (pintype "bidirectional"))
    )
    (net (code "111") (name "P9_06") (class "Default")
      (node (ref "U5") (pin "72") (pinfunction "P9_6_72") (pintype "bidirectional"))
    )
    (net (code "112") (name "P9_07") (class "Default")
      (node (ref "U5") (pin "71") (pinfunction "P9_7_71") (pintype "bidirectional"))
    )
    (net (code "113") (name "P9_08") (class "Default")
      (node (ref "U5") (pin "70") (pinfunction "P9_8_70") (pintype "bidirectional"))
    )
    (net (code "114") (name "P009_AN004") (class "Default")
      (node (ref "U5") (pin "160") (pinfunction "P0_9/AN004_160") (pintype "bidirectional"))
    )
    (net (code "115") (name "P014_DA0_AN005_AN105") (class "Default")
      (node (ref "U5") (pin "152") (pinfunction "P0_14/DA0/AN005/AN105_152") (pintype "bidirectional"))
    )
    (net (code "116") (name "P015_DA1_AN006_AN106") (class "Default")
      (node (ref "U5") (pin "151") (pinfunction "P0_15/DA1/AN006/AN106_151") (pintype "bidirectional"))
    )
    (net (code "117") (name "P400_ADC") (class "Default")
      (node (ref "U5") (pin "1") (pinfunction "P4_0_1") (pintype "bidirectional"))
    )
    (net (code "118") (name "PA_00") (class "Default")
      (node (ref "U5") (pin "114") (pinfunction "PA_0_114") (pintype "bidirectional"))
    )
    (net (code "119") (name "PA_01") (class "Default")
      (node (ref "U5") (pin "113") (pinfunction "PA_1_113") (pintype "bidirectional"))
    )
    (net (code "120") (name "PA_08") (class "Default")
      (node (ref "U5") (pin "107") (pinfunction "PA_8_107") (pintype "bidirectional"))
    )
    (net (code "121") (name "PA_09") (class "Default")
      (node (ref "U5") (pin "108") (pinfunction "PA_9_108") (pintype "bidirectional"))
    )
    (net (code "122") (name "PA_10") (class "Default")
      (node (ref "U5") (pin "109") (pinfunction "PA_10_109") (pintype "bidirectional"))
    )
    (net (code "123") (name "RELAY_1") (class "Default")
      (node (ref "J4") (pin "P$15") (pinfunction "P$15_P$15") (pintype "bidirectional"))
      (node (ref "U5") (pin "68") (pinfunction "P2_1/MD_68") (pintype "bidirectional"))
    )
    (net (code "124") (name "RELAY_2") (class "Default")
      (node (ref "J4") (pin "P$17") (pinfunction "P$17_P$17") (pintype "bidirectional"))
      (node (ref "U5") (pin "54") (pinfunction "P2_2_54") (pintype "bidirectional"))
    )
    (net (code "125") (name "RELAY_3") (class "Default")
      (node (ref "J4") (pin "P$19") (pinfunction "P$19_P$19") (pintype "bidirectional"))
      (node (ref "U5") (pin "53") (pinfunction "P2_3_53") (pintype "bidirectional"))
    )
    (net (code "126") (name "RELAY_4") (class "Default")
      (node (ref "J4") (pin "P$20") (pinfunction "P$20_P$20") (pintype "bidirectional"))
      (node (ref "U5") (pin "52") (pinfunction "P2_4_52") (pintype "bidirectional"))
    )
    (net (code "127") (name "RESET") (class "Default")
      (node (ref "C29") (pin "P$1") (pinfunction "1_P$1") (pintype "passive"))
      (node (ref "J1") (pin "9") (pinfunction "9_9") (pintype "passive"))
      (node (ref "R10") (pin "P$1") (pinfunction "1_P$1") (pintype "passive"))
      (node (ref "U5") (pin "67") (pinfunction "RES#_67") (pintype "bidirectional"))
    )
    (net (code "128") (name "TCK") (class "Default")
      (node (ref "J1") (pin "7") (pinfunction "7_7") (pintype "passive"))
      (node (ref "U5") (pin "88") (pinfunction "P3_0_88") (pintype "bidirectional"))
    )
    (net (code "129") (name "TDI") (class "Default")
      (node (ref "J1") (pin "1") (pinfunction "1_1") (pintype "passive"))
      (node (ref "U5") (pin "91") (pinfunction "P1_10_91") (pintype "bidirectional"))
    )
    (net (code "130") (name "TDO") (class "Default")
      (node (ref "J1") (pin "3") (pinfunction "3_3") (pintype "passive"))
      (node (ref "U5") (pin "90") (pinfunction "P1_9_90") (pintype "bidirectional"))
    )
    (net (code "131") (name "TMS") (class "Default")
      (node (ref "J1") (pin "5") (pinfunction "5_5") (pintype "passive"))
      (node (ref "U5") (pin "89") (pinfunction "P1_8_89") (pintype "bidirectional"))
    )
    (net (code "132") (name "USBHS_FAULT") (class "Default")
      (node (ref "R2") (pin "P$1") (pinfunction "1_P$1") (pintype "passive"))
      (node (ref "U2") (pin "3") (pinfunction "FLG_3") (pintype "input"))
      (node (ref "U5") (pin "78") (pinfunction "P3_8_78") (pintype "bidirectional"))
    )
    (net (code "133") (name "USBHS_N") (class "Default")
      (node (ref "U5") (pin "31") (pinfunction "USBHS_DM_31") (pintype "bidirectional"))
      (node (ref "USB1") (pin "D-") (pinfunction "D-_D-") (pintype "bidirectional"))
    )
    (net (code "134") (name "USBHS_P") (class "Default")
      (node (ref "U5") (pin "32") (pinfunction "USBHS_DP_32") (pintype "bidirectional"))
      (node (ref "USB1") (pin "D+") (pinfunction "D+_D+") (pintype "bidirectional"))
    )
    (net (code "135") (name "USBHS_VBUS") (class "Default")
      (node (ref "C15") (pin "P$1") (pinfunction "1_P$1") (pintype "passive"))
      (node (ref "C18") (pin "1") (pinfunction "1_1") (pintype "passive"))
      (node (ref "U2") (pin "5") (pinfunction "OUT_5") (pintype "input"))
      (node (ref "U5") (pin "17") (pinfunction "PB_1_17") (pintype "bidirectional"))
      (node (ref "USB1") (pin "VBUS") (pinfunction "VBUS_VBUS") (pintype "power_in"))
    )
    (net (code "136") (name "USBHS_VBUSEN") (class "Default")
      (node (ref "R3") (pin "P$1") (pinfunction "1_P$1") (pintype "passive"))
      (node (ref "U2") (pin "1") (pinfunction "EN_1") (pintype "input"))
      (node (ref "U5") (pin "16") (pinfunction "PB_0_16") (pintype "bidirectional"))
    )
    (net (code "137") (name "USB_N") (class "Default")
      (node (ref "R5") (pin "P$1") (pinfunction "1_P$1") (pintype "passive"))
      (node (ref "U5") (pin "46") (pinfunction "USB_DM_46") (pintype "bidirectional"))
    )
    (net (code "138") (name "USB_P") (class "Default")
      (node (ref "R6") (pin "P$1") (pinfunction "1_P$1") (pintype "passive"))
      (node (ref "U5") (pin "47") (pinfunction "USB_DP_47") (pintype "bidirectional"))
    )
    (net (code "139") (name "USB_VBUS_B") (class "Default")
      (node (ref "R4") (pin "P$1") (pinfunction "1_P$1") (pintype "passive"))
      (node (ref "U5") (pin "44") (pinfunction "P4_7_44") (pintype "bidirectional"))
    )
    (net (code "140") (name "VCL_F(FLASH)") (class "Default")
      (node (ref "C21") (pin "P$2") (pinfunction "2_P$2") (pintype "passive"))
      (node (ref "U5") (pin "112") (pinfunction "VCL_F(FLASH)_112") (pintype "bidirectional"))
    )
    (net (code "141") (name "VDD") (class "Default")
      (node (ref "C10") (pin "P$2") (pinfunction "2_P$2") (pintype "passive"))
      (node (ref "C12") (pin "P$2") (pinfunction "2_P$2") (pintype "passive"))
      (node (ref "C13") (pin "P$2") (pinfunction "2_P$2") (pintype "passive"))
      (node (ref "C17") (pin "P$2") (pinfunction "2_P$2") (pintype "passive"))
      (node (ref "C2") (pin "P$1") (pinfunction "1_P$1") (pintype "passive"))
      (node (ref "C22") (pin "P$2") (pinfunction "2_P$2") (pintype "passive"))
      (node (ref "C23") (pin "P$1") (pinfunction "1_P$1") (pintype "passive"))
      (node (ref "C25") (pin "P$2") (pinfunction "2_P$2") (pintype "passive"))
      (node (ref "C26") (pin "P$1") (pinfunction "1_P$1") (pintype "passive"))
      (node (ref "C27") (pin "P$1") (pinfunction "1_P$1") (pintype "passive"))
      (node (ref "C3") (pin "P$1") (pinfunction "1_P$1") (pintype "passive"))
      (node (ref "C30") (pin "P$1") (pinfunction "1_P$1") (pintype "passive"))
      (node (ref "C31") (pin "P$2") (pinfunction "2_P$2") (pintype "passive"))
      (node (ref "C4") (pin "P$1") (pinfunction "1_P$1") (pintype "passive"))
      (node (ref "C6") (pin "P$2") (pinfunction "2_P$2") (pintype "passive"))
      (node (ref "J1") (pin "2") (pinfunction "2_2") (pintype "passive"))
      (node (ref "J1") (pin "4") (pinfunction "4_4") (pintype "passive"))
      (node (ref "J2") (pin "P$1") (pinfunction "3.3V_P$1") (pintype "power_in"))
      (node (ref "J2") (pin "P$17") (pinfunction "3.3V_P$17") (pintype "power_in"))
      (node (ref "L1") (pin "2") (pinfunction "P$2_2") (pintype "bidirectional"))
      (node (ref "R1") (pin "P$2") (pinfunction "2_P$2") (pintype "passive"))
      (node (ref "R10") (pin "P$2") (pinfunction "2_P$2") (pintype "passive"))
      (node (ref "R12") (pin "P$1") (pinfunction "1_P$1") (pintype "passive"))
      (node (ref "R13") (pin "P$1") (pinfunction "1_P$1") (pintype "passive"))
      (node (ref "U5") (pin "110") (pinfunction "VCC(IO)5_110") (pintype "bidirectional"))
      (node (ref "U5") (pin "123") (pinfunction "VCC(IO)6_123") (pintype "bidirectional"))
      (node (ref "U5") (pin "138") (pinfunction "VCC(IO)7_138") (pintype "bidirectional"))
      (node (ref "U5") (pin "149") (pinfunction "VCC(IO)8_149") (pintype "bidirectional"))
      (node (ref "U5") (pin "155") (pinfunction "AVCC0_155") (pintype "bidirectional"))
      (node (ref "U5") (pin "171") (pinfunction "VCC(IO)9_171") (pintype "bidirectional"))
      (node (ref "U5") (pin "25") (pinfunction "VCC1_25") (pintype "bidirectional"))
      (node (ref "U5") (pin "26") (pinfunction "AVCC_SUBHS_26") (pintype "bidirectional"))
      (node (ref "U5") (pin "34") (pinfunction "VCC_USBHS_34") (pintype "bidirectional"))
      (node (ref "U5") (pin "48") (pinfunction "VCC_USB_48") (pintype "bidirectional"))
      (node (ref "U5") (pin "61") (pinfunction "VCC(IO)2_61") (pintype "bidirectional"))
      (node (ref "U5") (pin "84") (pinfunction "VCC(IO)3_84") (pintype "bidirectional"))
      (node (ref "U5") (pin "97") (pinfunction "VCC(IO)4_97") (pintype "bidirectional"))
    )
    (net (code "142") (name "VDD5") (class "Default")
      (node (ref "C11") (pin "P$1") (pinfunction "1_P$1") (pintype "passive"))
      (node (ref "C8") (pin "P$1") (pinfunction "1_P$1") (pintype "passive"))
      (node (ref "J2") (pin "P$2") (pinfunction "5V_P$2") (pintype "power_in"))
      (node (ref "J2") (pin "P$4") (pinfunction "5V_P$4") (pintype "power_in"))
      (node (ref "J3") (pin "P$3") (pinfunction "P$3_P$3") (pintype "bidirectional"))
      (node (ref "R2") (pin "P$2") (pinfunction "2_P$2") (pintype "passive"))
      (node (ref "R3") (pin "P$2") (pinfunction "2_P$2") (pintype "passive"))
      (node (ref "U2") (pin "4") (pinfunction "VIN_4") (pintype "input"))
    )
    (net (code "143") (name "VDDIN") (class "Default")
      (node (ref "J3") (pin "P$2") (pinfunction "P$2_P$2") (pintype "bidirectional"))
      (node (ref "L1") (pin "1") (pinfunction "P$1_1") (pintype "bidirectional"))
    )
    (net (code "144") (name "XCIN") (class "Default")
      (node (ref "C19") (pin "P$1") (pinfunction "1_P$1") (pintype "passive"))
      (node (ref "U5") (pin "20") (pinfunction "XCIN_20") (pintype "bidirectional"))
      (node (ref "X2") (pin "P$1") (pinfunction "P$1_P$1") (pintype "bidirectional"))
    )
    (net (code "145") (name "XCOUT") (class "Default")
      (node (ref "C24") (pin "P$1") (pinfunction "1_P$1") (pintype "passive"))
      (node (ref "U5") (pin "21") (pinfunction "XCOUT_21") (pintype "bidirectional"))
      (node (ref "X2") (pin "P$2") (pinfunction "P$2_P$2") (pintype "bidirectional"))
    )
    (net (code "146") (name "XTAL1") (class "Default")
      (node (ref "C7") (pin "P$1") (pinfunction "1_P$1") (pintype "passive"))
      (node (ref "U5") (pin "23") (pinfunction "P2_13/XTAL_23") (pintype "bidirectional"))
      (node (ref "X1") (pin "1") (pinfunction "1_1") (pintype "bidirectional"))
    )
    (net (code "147") (name "XTAL2") (class "Default")
      (node (ref "C14") (pin "P$1") (pinfunction "1_P$1") (pintype "passive"))
      (node (ref "U5") (pin "24") (pinfunction "P2_12/EXTAL_24") (pintype "bidirectional"))
      (node (ref "X1") (pin "3") (pinfunction "3_3") (pintype "bidirectional"))
    )
    (net (code "148") (name "X_DIR") (class "Default")
      (node (ref "J4") (pin "P$3") (pinfunction "P$3_P$3") (pintype "bidirectional"))
      (node (ref "U5") (pin "118") (pinfunction "P6_4_118") (pintype "bidirectional"))
    )
    (net (code "149") (name "X_LS") (class "Default")
      (node (ref "J4") (pin "P$2") (pinfunction "P$2_P$2") (pintype "bidirectional"))
      (node (ref "U5") (pin "164") (pinfunction "P0_5/AN101_164") (pintype "bidirectional"))
    )
    (net (code "150") (name "X_STEP") (class "Default")
      (node (ref "J4") (pin "P$11") (pinfunction "P$11_P$11") (pintype "bidirectional"))
      (node (ref "U5") (pin "86") (pinfunction "P3_2_86") (pintype "bidirectional"))
    )
    (net (code "151") (name "Y_DIR") (class "Default")
      (node (ref "J4") (pin "P$5") (pinfunction "P$5_P$5") (pintype "bidirectional"))
      (node (ref "U5") (pin "115") (pinfunction "P6_7_115") (pintype "bidirectional"))
    )
    (net (code "152") (name "Y_LS") (class "Default")
      (node (ref "J4") (pin "P$4") (pinfunction "P$4_P$4") (pintype "bidirectional"))
      (node (ref "U5") (pin "175") (pinfunction "P5_12_175") (pintype "bidirectional"))
    )
    (net (code "153") (name "Y_STEP") (class "Default")
      (node (ref "J4") (pin "P$13") (pinfunction "P$13_P$13") (pintype "bidirectional"))
      (node (ref "U5") (pin "82") (pinfunction "P3_4_82") (pintype "bidirectional"))
    )
    (net (code "154") (name "Z_DIR") (class "Default")
      (node (ref "J4") (pin "P$1") (pinfunction "P$1_P$1") (pintype "bidirectional"))
      (node (ref "U5") (pin "121") (pinfunction "P6_1_121") (pintype "bidirectional"))
    )
    (net (code "155") (name "Z_LS") (class "Default")
      (node (ref "J4") (pin "P$6") (pinfunction "P$6_P$6") (pintype "bidirectional"))
      (node (ref "U5") (pin "169") (pinfunction "P0_0/AN0\\00_169") (pintype "bidirectional"))
    )
    (net (code "156") (name "Z_STEP") (class "Default")
      (node (ref "J4") (pin "P$9") (pinfunction "P$9_P$9") (pintype "bidirectional"))
      (node (ref "U5") (pin "92") (pinfunction "P1_11_92") (pintype "bidirectional"))
    )
    (net (code "157") (name "unconnected-(J2-CE0-PadP$24)") (class "Default")
      (node (ref "J2") (pin "P$24") (pinfunction "CE0_P$24") (pintype "output"))
    )
    (net (code "158") (name "unconnected-(J2-CE1-PadP$26)") (class "Default")
      (node (ref "J2") (pin "P$26") (pinfunction "CE1_P$26") (pintype "output"))
    )
    (net (code "159") (name "unconnected-(J2-ID_SC-PadP$28)") (class "Default")
      (node (ref "J2") (pin "P$28") (pinfunction "ID_SC_P$28") (pintype "bidirectional"))
    )
    (net (code "160") (name "unconnected-(J2-ID_SD-PadP$27)") (class "Default")
      (node (ref "J2") (pin "P$27") (pinfunction "ID_SD_P$27") (pintype "bidirectional"))
    )
    (net (code "161") (name "unconnected-(J2-MISO-PadP$21)") (class "Default")
      (node (ref "J2") (pin "P$21") (pinfunction "MISO_P$21") (pintype "input"))
    )
    (net (code "162") (name "unconnected-(J2-MOSI-PadP$19)") (class "Default")
      (node (ref "J2") (pin "P$19") (pinfunction "MOSI_P$19") (pintype "output"))
    )
    (net (code "163") (name "unconnected-(J2-RXI-PadP$10)") (class "Default")
      (node (ref "J2") (pin "P$10") (pinfunction "RXI_P$10") (pintype "input"))
    )
    (net (code "164") (name "unconnected-(J2-SCLK-PadP$23)") (class "Default")
      (node (ref "J2") (pin "P$23") (pinfunction "SCLK_P$23") (pintype "output"))
    )
    (net (code "165") (name "unconnected-(J2-TXO-PadP$8)") (class "Default")
      (node (ref "J2") (pin "P$8") (pinfunction "TXO_P$8") (pintype "output"))
    )
    (net (code "166") (name "unconnected-(J5-PadP$1)") (class "Default")
      (node (ref "J5") (pin "P$1") (pinfunction "P$1_P$1") (pintype "bidirectional"))
    )
    (net (code "167") (name "unconnected-(J5-PadP$2)") (class "Default")
      (node (ref "J5") (pin "P$2") (pinfunction "P$2_P$2") (pintype "bidirectional"))
    )
    (net (code "168") (name "unconnected-(J5-PadP$3)") (class "Default")
      (node (ref "J5") (pin "P$3") (pinfunction "P$3_P$3") (pintype "bidirectional"))
    )
    (net (code "169") (name "unconnected-(J5-PadP$4)") (class "Default")
      (node (ref "J5") (pin "P$4") (pinfunction "P$4_P$4") (pintype "bidirectional"))
    )
    (net (code "170") (name "unconnected-(J5-PadP$5)") (class "Default")
      (node (ref "J5") (pin "P$5") (pinfunction "P$5_P$5") (pintype "bidirectional"))
    )
    (net (code "171") (name "unconnected-(J5-PadP$6)") (class "Default")
      (node (ref "J5") (pin "P$6") (pinfunction "P$6_P$6") (pintype "bidirectional"))
    )
    (net (code "172") (name "unconnected-(J5-PadP$7)") (class "Default")
      (node (ref "J5") (pin "P$7") (pinfunction "P$7_P$7") (pintype "bidirectional"))
    )
    (net (code "173") (name "unconnected-(J5-PadP$8)") (class "Default")
      (node (ref "J5") (pin "P$8") (pinfunction "P$8_P$8") (pintype "bidirectional"))
    )
    (net (code "174") (name "unconnected-(J5-PadP$9)") (class "Default")
      (node (ref "J5") (pin "P$9") (pinfunction "P$9_P$9") (pintype "bidirectional"))
    )
    (net (code "175") (name "unconnected-(J5-PadP$10)") (class "Default")
      (node (ref "J5") (pin "P$10") (pinfunction "P$10_P$10") (pintype "bidirectional"))
    )
    (net (code "176") (name "unconnected-(J5-PadP$11)") (class "Default")
      (node (ref "J5") (pin "P$11") (pinfunction "P$11_P$11") (pintype "bidirectional"))
    )
    (net (code "177") (name "unconnected-(J5-PadP$12)") (class "Default")
      (node (ref "J5") (pin "P$12") (pinfunction "P$12_P$12") (pintype "bidirectional"))
    )
    (net (code "178") (name "unconnected-(J5-PadP$13)") (class "Default")
      (node (ref "J5") (pin "P$13") (pinfunction "P$13_P$13") (pintype "bidirectional"))
    )
    (net (code "179") (name "unconnected-(J5-PadP$14)") (class "Default")
      (node (ref "J5") (pin "P$14") (pinfunction "P$14_P$14") (pintype "bidirectional"))
    )
    (net (code "180") (name "unconnected-(J5-PadP$15)") (class "Default")
      (node (ref "J5") (pin "P$15") (pinfunction "P$15_P$15") (pintype "bidirectional"))
    )
    (net (code "181") (name "unconnected-(J5-PadP$16)") (class "Default")
      (node (ref "J5") (pin "P$16") (pinfunction "P$16_P$16") (pintype "bidirectional"))
    )
    (net (code "182") (name "unconnected-(J5-PadP$17)") (class "Default")
      (node (ref "J5") (pin "P$17") (pinfunction "P$17_P$17") (pintype "bidirectional"))
    )
    (net (code "183") (name "unconnected-(J5-PadP$18)") (class "Default")
      (node (ref "J5") (pin "P$18") (pinfunction "P$18_P$18") (pintype "bidirectional"))
    )
    (net (code "184") (name "unconnected-(J5-PadP$19)") (class "Default")
      (node (ref "J5") (pin "P$19") (pinfunction "P$19_P$19") (pintype "bidirectional"))
    )
    (net (code "185") (name "unconnected-(J5-PadP$20)") (class "Default")
      (node (ref "J5") (pin "P$20") (pinfunction "P$20_P$20") (pintype "bidirectional"))
    )
    (net (code "186") (name "unconnected-(J5-PadP$21)") (class "Default")
      (node (ref "J5") (pin "P$21") (pinfunction "P$21_P$21") (pintype "bidirectional"))
    )
    (net (code "187") (name "unconnected-(J5-PadP$22)") (class "Default")
      (node (ref "J5") (pin "P$22") (pinfunction "P$22_P$22") (pintype "bidirectional"))
    )
    (net (code "188") (name "unconnected-(J5-PadP$23)") (class "Default")
      (node (ref "J5") (pin "P$23") (pinfunction "P$23_P$23") (pintype "bidirectional"))
    )
    (net (code "189") (name "unconnected-(J5-PadP$24)") (class "Default")
      (node (ref "J5") (pin "P$24") (pinfunction "P$24_P$24") (pintype "bidirectional"))
    )
    (net (code "190") (name "unconnected-(J5-PadP$25)") (class "Default")
      (node (ref "J5") (pin "P$25") (pinfunction "P$25_P$25") (pintype "bidirectional"))
    )
    (net (code "191") (name "unconnected-(J5-PadP$26)") (class "Default")
      (node (ref "J5") (pin "P$26") (pinfunction "P$26_P$26") (pintype "bidirectional"))
    )
    (net (code "192") (name "unconnected-(J5-PadP$27)") (class "Default")
      (node (ref "J5") (pin "P$27") (pinfunction "P$27_P$27") (pintype "bidirectional"))
    )
    (net (code "193") (name "unconnected-(J5-PadP$28)") (class "Default")
      (node (ref "J5") (pin "P$28") (pinfunction "P$28_P$28") (pintype "bidirectional"))
    )
    (net (code "194") (name "unconnected-(J5-PadP$29)") (class "Default")
      (node (ref "J5") (pin "P$29") (pinfunction "P$29_P$29") (pintype "bidirectional"))
    )
    (net (code "195") (name "unconnected-(J5-PadP$30)") (class "Default")
      (node (ref "J5") (pin "P$30") (pinfunction "P$30_P$30") (pintype "bidirectional"))
    )
    (net (code "196") (name "unconnected-(J5-PadP$31)") (class "Default")
      (node (ref "J5") (pin "P$31") (pinfunction "P$31_P$31") (pintype "bidirectional"))
    )
    (net (code "197") (name "unconnected-(J5-PadP$32)") (class "Default")
      (node (ref "J5") (pin "P$32") (pinfunction "P$32_P$32") (pintype "bidirectional"))
    )
    (net (code "198") (name "unconnected-(J5-PadP$33)") (class "Default")
      (node (ref "J5") (pin "P$33") (pinfunction "P$33_P$33") (pintype "bidirectional"))
    )
    (net (code "199") (name "unconnected-(J5-PadP$34)") (class "Default")
      (node (ref "J5") (pin "P$34") (pinfunction "P$34_P$34") (pintype "bidirectional"))
    )
    (net (code "200") (name "unconnected-(J5-PadP$35)") (class "Default")
      (node (ref "J5") (pin "P$35") (pinfunction "P$35_P$35") (pintype "bidirectional"))
    )
    (net (code "201") (name "unconnected-(J5-PadP$36)") (class "Default")
      (node (ref "J5") (pin "P$36") (pinfunction "P$36_P$36") (pintype "bidirectional"))
    )
    (net (code "202") (name "unconnected-(J5-PadP$37)") (class "Default")
      (node (ref "J5") (pin "P$37") (pinfunction "P$37_P$37") (pintype "bidirectional"))
    )
    (net (code "203") (name "unconnected-(J5-PadP$38)") (class "Default")
      (node (ref "J5") (pin "P$38") (pinfunction "P$38_P$38") (pintype "bidirectional"))
    )
    (net (code "204") (name "unconnected-(J5-PadP$39)") (class "Default")
      (node (ref "J5") (pin "P$39") (pinfunction "P$39_P$39") (pintype "bidirectional"))
    )
    (net (code "205") (name "unconnected-(J5-PadP$40)") (class "Default")
      (node (ref "J5") (pin "P$40") (pinfunction "P$40_P$40") (pintype "bidirectional"))
    )
    (net (code "206") (name "unconnected-(J6-PadP$1)") (class "Default")
      (node (ref "J6") (pin "P$1") (pinfunction "P$1_P$1") (pintype "bidirectional"))
    )
    (net (code "207") (name "unconnected-(J6-PadP$2)") (class "Default")
      (node (ref "J6") (pin "P$2") (pinfunction "P$2_P$2") (pintype "bidirectional"))
    )
    (net (code "208") (name "unconnected-(J6-PadP$3)") (class "Default")
      (node (ref "J6") (pin "P$3") (pinfunction "P$3_P$3") (pintype "bidirectional"))
    )
    (net (code "209") (name "unconnected-(J6-PadP$4)") (class "Default")
      (node (ref "J6") (pin "P$4") (pinfunction "P$4_P$4") (pintype "bidirectional"))
    )
    (net (code "210") (name "unconnected-(J6-PadP$5)") (class "Default")
      (node (ref "J6") (pin "P$5") (pinfunction "P$5_P$5") (pintype "bidirectional"))
    )
    (net (code "211") (name "unconnected-(J6-PadP$6)") (class "Default")
      (node (ref "J6") (pin "P$6") (pinfunction "P$6_P$6") (pintype "bidirectional"))
    )
    (net (code "212") (name "unconnected-(J6-PadP$7)") (class "Default")
      (node (ref "J6") (pin "P$7") (pinfunction "P$7_P$7") (pintype "bidirectional"))
    )
    (net (code "213") (name "unconnected-(J6-PadP$8)") (class "Default")
      (node (ref "J6") (pin "P$8") (pinfunction "P$8_P$8") (pintype "bidirectional"))
    )
    (net (code "214") (name "unconnected-(J6-PadP$9)") (class "Default")
      (node (ref "J6") (pin "P$9") (pinfunction "P$9_P$9") (pintype "bidirectional"))
    )
    (net (code "215") (name "unconnected-(J6-PadP$10)") (class "Default")
      (node (ref "J6") (pin "P$10") (pinfunction "P$10_P$10") (pintype "bidirectional"))
    )
    (net (code "216") (name "unconnected-(J6-PadP$11)") (class "Default")
      (node (ref "J6") (pin "P$11") (pinfunction "P$11_P$11") (pintype "bidirectional"))
    )
    (net (code "217") (name "unconnected-(J6-PadP$12)") (class "Default")
      (node (ref "J6") (pin "P$12") (pinfunction "P$12_P$12") (pintype "bidirectional"))
    )
    (net (code "218") (name "unconnected-(J6-PadP$13)") (class "Default")
      (node (ref "J6") (pin "P$13") (pinfunction "P$13_P$13") (pintype "bidirectional"))
    )
    (net (code "219") (name "unconnected-(J6-PadP$14)") (class "Default")
      (node (ref "J6") (pin "P$14") (pinfunction "P$14_P$14") (pintype "bidirectional"))
    )
    (net (code "220") (name "unconnected-(J6-PadP$15)") (class "Default")
      (node (ref "J6") (pin "P$15") (pinfunction "P$15_P$15") (pintype "bidirectional"))
    )
    (net (code "221") (name "unconnected-(J6-PadP$16)") (class "Default")
      (node (ref "J6") (pin "P$16") (pinfunction "P$16_P$16") (pintype "bidirectional"))
    )
    (net (code "222") (name "unconnected-(J6-PadP$17)") (class "Default")
      (node (ref "J6") (pin "P$17") (pinfunction "P$17_P$17") (pintype "bidirectional"))
    )
    (net (code "223") (name "unconnected-(J6-PadP$18)") (class "Default")
      (node (ref "J6") (pin "P$18") (pinfunction "P$18_P$18") (pintype "bidirectional"))
    )
    (net (code "224") (name "unconnected-(J6-PadP$19)") (class "Default")
      (node (ref "J6") (pin "P$19") (pinfunction "P$19_P$19") (pintype "bidirectional"))
    )
    (net (code "225") (name "unconnected-(J6-PadP$20)") (class "Default")
      (node (ref "J6") (pin "P$20") (pinfunction "P$20_P$20") (pintype "bidirectional"))
    )
    (net (code "226") (name "unconnected-(J6-PadP$21)") (class "Default")
      (node (ref "J6") (pin "P$21") (pinfunction "P$21_P$21") (pintype "bidirectional"))
    )
    (net (code "227") (name "unconnected-(J6-PadP$22)") (class "Default")
      (node (ref "J6") (pin "P$22") (pinfunction "P$22_P$22") (pintype "bidirectional"))
    )
    (net (code "228") (name "unconnected-(J6-PadP$23)") (class "Default")
      (node (ref "J6") (pin "P$23") (pinfunction "P$23_P$23") (pintype "bidirectional"))
    )
    (net (code "229") (name "unconnected-(J6-PadP$24)") (class "Default")
      (node (ref "J6") (pin "P$24") (pinfunction "P$24_P$24") (pintype "bidirectional"))
    )
    (net (code "230") (name "unconnected-(J6-PadP$25)") (class "Default")
      (node (ref "J6") (pin "P$25") (pinfunction "P$25_P$25") (pintype "bidirectional"))
    )
    (net (code "231") (name "unconnected-(J6-PadP$26)") (class "Default")
      (node (ref "J6") (pin "P$26") (pinfunction "P$26_P$26") (pintype "bidirectional"))
    )
    (net (code "232") (name "unconnected-(J6-PadP$27)") (class "Default")
      (node (ref "J6") (pin "P$27") (pinfunction "P$27_P$27") (pintype "bidirectional"))
    )
    (net (code "233") (name "unconnected-(J6-PadP$28)") (class "Default")
      (node (ref "J6") (pin "P$28") (pinfunction "P$28_P$28") (pintype "bidirectional"))
    )
    (net (code "234") (name "unconnected-(J6-PadP$29)") (class "Default")
      (node (ref "J6") (pin "P$29") (pinfunction "P$29_P$29") (pintype "bidirectional"))
    )
    (net (code "235") (name "unconnected-(J6-PadP$30)") (class "Default")
      (node (ref "J6") (pin "P$30") (pinfunction "P$30_P$30") (pintype "bidirectional"))
    )
    (net (code "236") (name "unconnected-(J6-PadP$31)") (class "Default")
      (node (ref "J6") (pin "P$31") (pinfunction "P$31_P$31") (pintype "bidirectional"))
    )
    (net (code "237") (name "unconnected-(J6-PadP$32)") (class "Default")
      (node (ref "J6") (pin "P$32") (pinfunction "P$32_P$32") (pintype "bidirectional"))
    )
    (net (code "238") (name "unconnected-(J6-PadP$33)") (class "Default")
      (node (ref "J6") (pin "P$33") (pinfunction "P$33_P$33") (pintype "bidirectional"))
    )
    (net (code "239") (name "unconnected-(J6-PadP$34)") (class "Default")
      (node (ref "J6") (pin "P$34") (pinfunction "P$34_P$34") (pintype "bidirectional"))
    )
    (net (code "240") (name "unconnected-(J6-PadP$35)") (class "Default")
      (node (ref "J6") (pin "P$35") (pinfunction "P$35_P$35") (pintype "bidirectional"))
    )
    (net (code "241") (name "unconnected-(J6-PadP$36)") (class "Default")
      (node (ref "J6") (pin "P$36") (pinfunction "P$36_P$36") (pintype "bidirectional"))
    )
    (net (code "242") (name "unconnected-(J6-PadP$37)") (class "Default")
      (node (ref "J6") (pin "P$37") (pinfunction "P$37_P$37") (pintype "bidirectional"))
    )
    (net (code "243") (name "unconnected-(J6-PadP$39)") (class "Default")
      (node (ref "J6") (pin "P$39") (pinfunction "P$39_P$39") (pintype "bidirectional"))
    )
    (net (code "244") (name "unconnected-(U5-P4_1-Pad2)") (class "Default")
      (node (ref "U5") (pin "2") (pinfunction "P4_1_2") (pintype "bidirectional"))
    )
    (net (code "245") (name "unconnected-(U5-P4_2-Pad3)") (class "Default")
      (node (ref "U5") (pin "3") (pinfunction "P4_2_3") (pintype "bidirectional"))
    )
    (net (code "246") (name "unconnected-(U5-P4_8-Pad43)") (class "Default")
      (node (ref "U5") (pin "43") (pinfunction "P4_8_43") (pintype "bidirectional"))
    )
    (net (code "247") (name "unconnected-(U5-P4_10-Pad41)") (class "Default")
      (node (ref "U5") (pin "41") (pinfunction "P4_10_41") (pintype "bidirectional"))
    )
    (net (code "248") (name "unconnected-(U5-P4_11-Pad40)") (class "Default")
      (node (ref "U5") (pin "40") (pinfunction "P4_11_40") (pintype "bidirectional"))
    )
    (net (code "249") (name "unconnected-(U5-P4_12-Pad39)") (class "Default")
      (node (ref "U5") (pin "39") (pinfunction "P4_12_39") (pintype "bidirectional"))
    )
    (net (code "250") (name "unconnected-(U5-P4_13-Pad38)") (class "Default")
      (node (ref "U5") (pin "38") (pinfunction "P4_13_38") (pintype "bidirectional"))
    )
    (net (code "251") (name "unconnected-(U5-P4_14-Pad37)") (class "Default")
      (node (ref "U5") (pin "37") (pinfunction "P4_14_37") (pintype "bidirectional"))
    )
    (net (code "252") (name "unconnected-(U5-P4_15-Pad36)") (class "Default")
      (node (ref "U5") (pin "36") (pinfunction "P4_15_36") (pintype "bidirectional"))
    )
    (net (code "253") (name "unconnected-(U5-P7_6-Pad14)") (class "Default")
      (node (ref "U5") (pin "14") (pinfunction "P7_6_14") (pintype "bidirectional"))
    )
    (net (code "254") (name "unconnected-(U5-P7_7-Pad15)") (class "Default")
      (node (ref "U5") (pin "15") (pinfunction "P7_7_15") (pintype "bidirectional"))
    )
    (net (code "255") (name "unconnected-(U5-VBAT-Pad18)") (class "Default")
      (node (ref "U5") (pin "18") (pinfunction "VBAT_18") (pintype "bidirectional"))
    )
    (net (code "256") (name "unconnected-(U5-VREFH-Pad154)") (class "Default")
      (node (ref "U5") (pin "154") (pinfunction "VREFH_154") (pintype "bidirectional"))
    )
    (net (code "257") (name "unconnected-(U5-VREFH0-Pad158)") (class "Default")
      (node (ref "U5") (pin "158") (pinfunction "VREFH0_158") (pintype "bidirectional"))
    )
    (net (code "258") (name "unconnected-(U5-VREFL-Pad153)") (class "Default")
      (node (ref "U5") (pin "153") (pinfunction "VREFL_153") (pintype "bidirectional"))
    )
    (net (code "259") (name "unconnected-(U5-VREFL0-Pad157)") (class "Default")
      (node (ref "U5") (pin "157") (pinfunction "VREFL0_157") (pintype "bidirectional"))
    )
  )
)
